# relay_driver.net
KiCad netlist of a schematic drawn in EAGLE
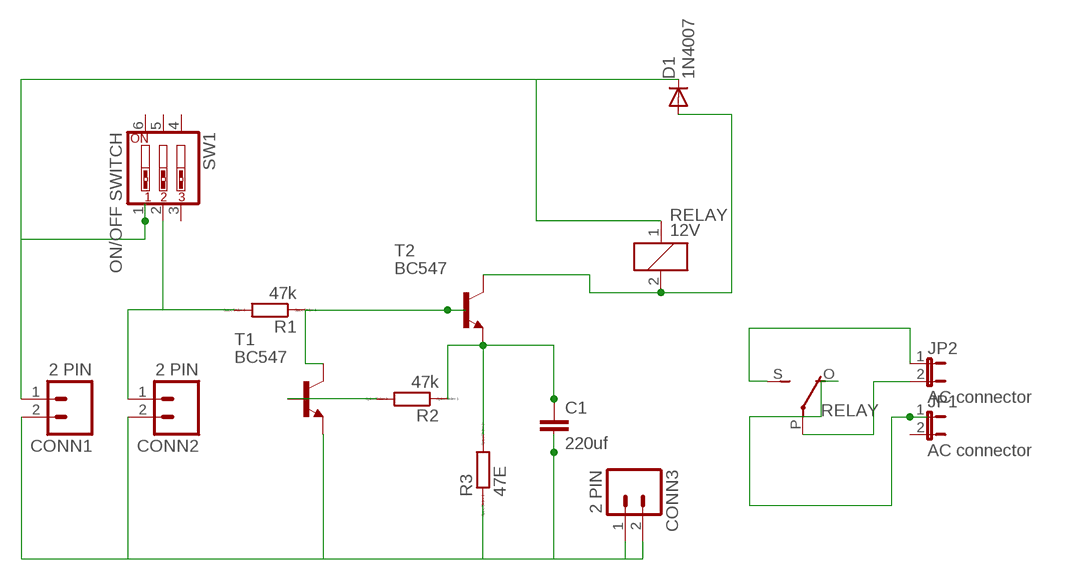
[diagram p0: schematic, sheet 1]

(export (version "E")
  (design (tool "Eeschema 10.0.6"))
  (components
    (comp (ref "C1")
      (value "220uf")
      (footprint "eagle-import:C2.5-5")
      (libsource (lib "eagle-import") (part "C2.5/5"))
    )
    (comp (ref "CONN1")
      (value "2 PIN")
      (footprint "eagle-import:02P")
      (libsource (lib "eagle-import") (part "M02"))
    )
    (comp (ref "CONN2")
      (value "2 PIN")
      (footprint "eagle-import:02P")
      (libsource (lib "eagle-import") (part "M02"))
    )
    (comp (ref "CONN3")
      (value "2 PIN")
      (footprint "eagle-import:02P")
      (libsource (lib "eagle-import") (part "M02"))
    )
    (comp (ref "D1")
      (value "1N4007")
      (footprint "eagle-import:DO41-10")
      (libsource (lib "eagle-import") (part "1N4004"))
    )
    (comp (ref "JP1")
      (value "AC connector")
      (footprint "eagle-import:JP1")
      (libsource (lib "eagle-import") (part "JP1E"))
    )
    (comp (ref "JP2")
      (value "AC connector")
      (footprint "eagle-import:JP1")
      (libsource (lib "eagle-import") (part "JP1E"))
    )
    (comp (ref "R1")
      (value "47k")
      (footprint "eagle-import:0204_7")
      (libsource (lib "eagle-import") (part "R0204/7"))
    )
    (comp (ref "R2")
      (value "47k")
      (footprint "eagle-import:0204_7")
      (libsource (lib "eagle-import") (part "R0204/7"))
    )
    (comp (ref "R3")
      (value "47E")
      (footprint "eagle-import:0204_7")
      (libsource (lib "eagle-import") (part "R0204/7"))
    )
    (comp (ref "RELAY")
      (value "12V")
      (footprint "eagle-import:G5LE")
      (libsource (lib "eagle-import") (part "G5L"))
    )
    (comp (ref "SW1")
      (value "ON/OFF SWITCH")
      (footprint "eagle-import:EDG-03")
      (libsource (lib "eagle-import") (part "SW_DIP-3"))
    )
    (comp (ref "T1")
      (value "BC547")
      (footprint "eagle-import:TO92")
      (libsource (lib "eagle-import") (part "BC547"))
    )
    (comp (ref "T2")
      (value "BC547")
      (footprint "eagle-import:TO92")
      (libsource (lib "eagle-import") (part "BC547"))
    )
  )
  (nets
    (net (code "1") (name "Net-(CONN1-Pad1)") (class "Default")
      (node (ref "CONN1") (pin "1") (pinfunction "1_1") (pintype "passive"))
      (node (ref "D1") (pin "C") (pinfunction "C_C") (pintype "passive"))
      (node (ref "RELAY") (pin "1") (pinfunction "1_1") (pintype "passive"))
      (node (ref "SW1") (pin "1") (pinfunction "1_1") (pintype "passive"))
    )
    (net (code "2") (name "Net-(CONN2-Pad1)") (class "Default")
      (node (ref "CONN2") (pin "1") (pinfunction "1_1") (pintype "passive"))
      (node (ref "R1") (pin "2") (pinfunction "2_2") (pintype "passive"))
      (node (ref "SW1") (pin "2") (pinfunction "2_2") (pintype "passive"))
    )
    (net (code "3") (name "Net-(JP1-Pad1)") (class "Default")
      (node (ref "JP1") (pin "1") (pinfunction "1_1") (pintype "passive"))
      (node (ref "RELAY") (pin "O") (pinfunction "O_O") (pintype "passive"))
    )
    (net (code "4") (name "Net-(JP2-Pad1)") (class "Default")
      (node (ref "JP2") (pin "1") (pinfunction "1_1") (pintype "passive"))
      (node (ref "RELAY") (pin "S") (pinfunction "S_S") (pintype "passive"))
    )
    (net (code "5") (name "Net-(JP2-Pad2)") (class "Default")
      (node (ref "JP2") (pin "2") (pinfunction "2_2") (pintype "passive"))
      (node (ref "RELAY") (pin "P") (pinfunction "P_P") (pintype "passive"))
    )
    (net (code "6") (name "Net-(T1-B)") (class "Default")
      (node (ref "R2") (pin "2") (pinfunction "2_2") (pintype "passive"))
      (node (ref "T1") (pin "2") (pinfunction "B_2") (pintype "passive"))
    )
    (net (code "7") (name "Net-(T1-C)") (class "Default")
      (node (ref "R1") (pin "1") (pinfunction "1_1") (pintype "passive"))
      (node (ref "T1") (pin "3") (pinfunction "C_3") (pintype "passive"))
      (node (ref "T2") (pin "2") (pinfunction "B_2") (pintype "passive"))
    )
    (net (code "8") (name "Net-(T1-E)") (class "Default")
      (node (ref "C1") (pin "2") (pinfunction "2_2") (pintype "passive"))
      (node (ref "CONN1") (pin "2") (pinfunction "2_2") (pintype "passive"))
      (node (ref "CONN2") (pin "2") (pinfunction "2_2") (pintype "passive"))
      (node (ref "CONN3") (pin "1") (pinfunction "1_1") (pintype "passive"))
      (node (ref "CONN3") (pin "2") (pinfunction "2_2") (pintype "passive"))
      (node (ref "R3") (pin "1") (pinfunction "1_1") (pintype "passive"))
      (node (ref "T1") (pin "1") (pinfunction "E_1") (pintype "passive"))
    )
    (net (code "9") (name "Net-(T2-C)") (class "Default")
      (node (ref "D1") (pin "A") (pinfunction "A_A") (pintype "passive"))
      (node (ref "RELAY") (pin "2") (pinfunction "2_2") (pintype "passive"))
      (node (ref "T2") (pin "3") (pinfunction "C_3") (pintype "passive"))
    )
    (net (code "10") (name "Net-(T2-E)") (class "Default")
      (node (ref "C1") (pin "1") (pinfunction "1_1") (pintype "passive"))
      (node (ref "R2") (pin "1") (pinfunction "1_1") (pintype "passive"))
      (node (ref "R3") (pin "2") (pinfunction "2_2") (pintype "passive"))
      (node (ref "T2") (pin "1") (pinfunction "E_1") (pintype "passive"))
    )
    (net (code "11") (name "unconnected-(JP1-Pad2)") (class "Default")
      (node (ref "JP1") (pin "2") (pinfunction "2_2") (pintype "passive"))
    )
    (net (code "12") (name "unconnected-(SW1-Pad3)") (class "Default")
      (node (ref "SW1") (pin "3") (pinfunction "3_3") (pintype "passive"))
    )
    (net (code "13") (name "unconnected-(SW1-Pad4)") (class "Default")
      (node (ref "SW1") (pin "4") (pinfunction "4_4") (pintype "passive"))
    )
    (net (code "14") (name "unconnected-(SW1-Pad5)") (class "Default")
      (node (ref "SW1") (pin "5") (pinfunction "5_5") (pintype "passive"))
    )
    (net (code "15") (name "unconnected-(SW1-Pad6)") (class "Default")
      (node (ref "SW1") (pin "6") (pinfunction "6_6") (pintype "passive"))
    )
  )
)
